# HCPL-3120_Gate_Driver_Circuit.net
KiCad netlist of a schematic drawn in Altium Designer
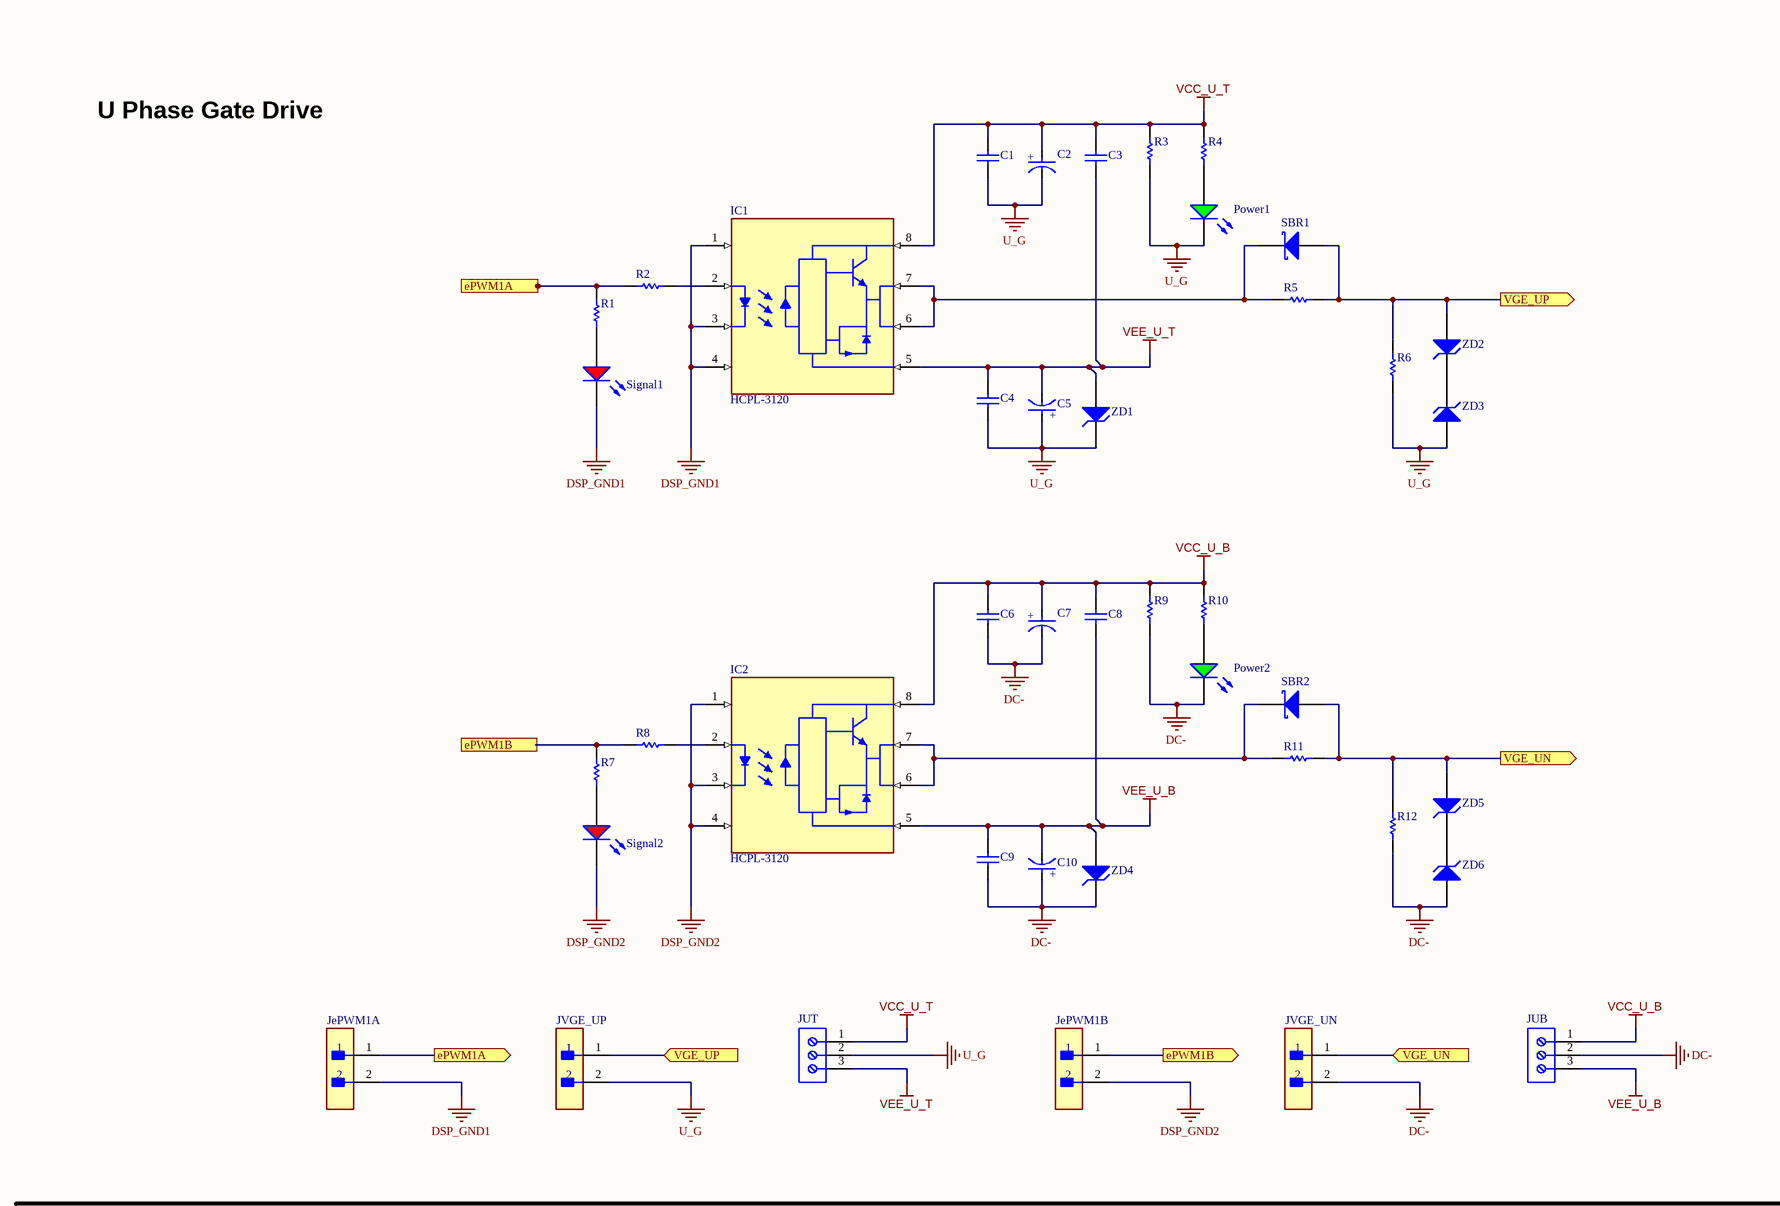
[diagram p0: HCPL-3120 Gate Driver Circuit.SchDoc, left]

(export (version "E")
  (design (tool "Eeschema 10.0.6"))
  (components
    (comp (ref "C1")
      (value "GRM188R71H104KA93D")
      (footprint "CAPC1608X90X35ML10T15")
      (description "Chip Capacitor, 0.1 uF, +/- 10%, 50 V, -55 to 125 degC, 0603 (1608 Metric), RoHS, Tape and Reel")
      (fields (field (name "TOLERANCE") "10%") (field (name "VOLTAGE") "50V"))
      (libsource (lib "Altium Content Vault") (part "CAP-NP-2"))
    )
    (comp (ref "C2")
      (value "EEUTA1H101")
      (footprint "FP-RAD-TH-D_10_0_5-L_12_5-MFG")
      (description "Aluminum Electrolytic Capacitors (Radial Lead Type) AEC-Q200 Qualified 100uF ±20% 50V")
      (fields (field (name "TOLERANCE") "20%"))
      (libsource (lib "Altium Content Vault") (part "203bc49f2ac43e59fd269a8c329ed05"))
    )
    (comp (ref "C3")
      (value "GRM188R71H104KA93D")
      (footprint "CAPC1608X90X35ML10T15")
      (description "Chip Capacitor, 0.1 uF, +/- 10%, 50 V, -55 to 125 degC, 0603 (1608 Metric), RoHS, Tape and Reel")
      (fields (field (name "TOLERANCE") "10%") (field (name "VOLTAGE") "50V"))
      (libsource (lib "Altium Content Vault") (part "CAP-NP-2"))
    )
    (comp (ref "C4")
      (value "GRM188R71H104KA93D")
      (footprint "CAPC1608X90X35ML10T15")
      (description "Chip Capacitor, 0.1 uF, +/- 10%, 50 V, -55 to 125 degC, 0603 (1608 Metric), RoHS, Tape and Reel")
      (fields (field (name "TOLERANCE") "10%") (field (name "VOLTAGE") "50V"))
      (libsource (lib "Altium Content Vault") (part "CAP-NP-2"))
    )
    (comp (ref "C5")
      (value "EEUTA1H101")
      (footprint "FP-RAD-TH-D_10_0_5-L_12_5-MFG")
      (description "Aluminum Electrolytic Capacitors (Radial Lead Type) AEC-Q200 Qualified 100uF ±20% 50V")
      (fields (field (name "TOLERANCE") "20%"))
      (libsource (lib "Altium Content Vault") (part "203bc49f2ac43e59fd269a8c329ed05"))
    )
    (comp (ref "C6")
      (value "GRM188R71H104KA93D")
      (footprint "CAPC1608X90X35ML10T15")
      (description "Chip Capacitor, 0.1 uF, +/- 10%, 50 V, -55 to 125 degC, 0603 (1608 Metric), RoHS, Tape and Reel")
      (fields (field (name "TOLERANCE") "10%") (field (name "VOLTAGE") "50V"))
      (libsource (lib "Altium Content Vault") (part "CAP-NP-2"))
    )
    (comp (ref "C7")
      (value "EEUTA1H101")
      (footprint "FP-RAD-TH-D_10_0_5-L_12_5-MFG")
      (description "Aluminum Electrolytic Capacitors (Radial Lead Type) AEC-Q200 Qualified 100uF ±20% 50V")
      (fields (field (name "TOLERANCE") "20%"))
      (libsource (lib "Altium Content Vault") (part "203bc49f2ac43e59fd269a8c329ed05"))
    )
    (comp (ref "C8")
      (value "GRM188R71H104KA93D")
      (footprint "CAPC1608X90X35ML10T15")
      (description "Chip Capacitor, 0.1 uF, +/- 10%, 50 V, -55 to 125 degC, 0603 (1608 Metric), RoHS, Tape and Reel")
      (fields (field (name "TOLERANCE") "10%") (field (name "VOLTAGE") "50V"))
      (libsource (lib "Altium Content Vault") (part "CAP-NP-2"))
    )
    (comp (ref "C9")
      (value "GRM188R71H104KA93D")
      (footprint "CAPC1608X90X35ML10T15")
      (description "Chip Capacitor, 0.1 uF, +/- 10%, 50 V, -55 to 125 degC, 0603 (1608 Metric), RoHS, Tape and Reel")
      (fields (field (name "TOLERANCE") "10%") (field (name "VOLTAGE") "50V"))
      (libsource (lib "Altium Content Vault") (part "CAP-NP-2"))
    )
    (comp (ref "C10")
      (value "EEUTA1H101")
      (footprint "FP-RAD-TH-D_10_0_5-L_12_5-MFG")
      (description "Aluminum Electrolytic Capacitors (Radial Lead Type) AEC-Q200 Qualified 100uF ±20% 50V")
      (fields (field (name "TOLERANCE") "20%"))
      (libsource (lib "Altium Content Vault") (part "203bc49f2ac43e59fd269a8c329ed05"))
    )
    (comp (ref "IC1")
      (value "HCPL-3120")
      (footprint "FP-DIP-8-MFG")
      (description "Optocoupler Drive Push-Pull 1-CH 30V 1500V 8-Pin PDIP Tube")
      (libsource (lib "HCPL_3210") (part "HCPL-3120"))
    )
    (comp (ref "IC2")
      (value "HCPL-3120")
      (footprint "FP-DIP-8-MFG")
      (description "Optocoupler Drive Push-Pull 1-CH 30V 1500V 8-Pin PDIP Tube")
      (libsource (lib "HCPL_3210") (part "HCPL-3120"))
    )
    (comp (ref "JePWM1A")
      (value "TSW-102-07-L-S")
      (footprint "FP-TSW-102-07-L-S-MFG")
      (description "CONN HEADER VERT 2POS 2.54MM")
      (libsource (lib "Altium Content Vault") (part "3bc925449376181038e59eaffc5286c"))
    )
    (comp (ref "JePWM1B")
      (value "TSW-102-07-L-S")
      (footprint "FP-TSW-102-07-L-S-MFG")
      (description "CONN HEADER VERT 2POS 2.54MM")
      (libsource (lib "Altium Content Vault") (part "3bc925449376181038e59eaffc5286c"))
    )
    (comp (ref "JUB")
      (value "691214110003")
      (footprint "691214110003")
      (fields (field (name "VOLTAGE") "300V"))
      (libsource (lib "Altium Content Vault") (part "TBL - 1R - 03P - Screw"))
    )
    (comp (ref "JUT")
      (value "691214110003")
      (footprint "691214110003")
      (fields (field (name "VOLTAGE") "300V"))
      (libsource (lib "Altium Content Vault") (part "TBL - 1R - 03P - Screw"))
    )
    (comp (ref "JVGE_UN")
      (value "TSW-102-07-L-S")
      (footprint "FP-TSW-102-07-L-S-MFG")
      (description "CONN HEADER VERT 2POS 2.54MM")
      (libsource (lib "Altium Content Vault") (part "3bc925449376181038e59eaffc5286c"))
    )
    (comp (ref "JVGE_UP")
      (value "TSW-102-07-L-S")
      (footprint "FP-TSW-102-07-L-S-MFG")
      (description "CONN HEADER VERT 2POS 2.54MM")
      (libsource (lib "Altium Content Vault") (part "3bc925449376181038e59eaffc5286c"))
    )
    (comp (ref "Power1")
      (value "151031VS04000")
      (footprint "WL-TMRC_D3.95H5.3")
      (description "Led, Green, T-1 (3Mm), 570 Nm, 2.1 V, 30 Ma, 120 Mcd")
      (libsource (lib "Altium Content Vault") (part "LED_Green_1A-2K"))
    )
    (comp (ref "Power2")
      (value "151031VS04000")
      (footprint "WL-TMRC_D3.95H5.3")
      (description "Led, Green, T-1 (3Mm), 570 Nm, 2.1 V, 30 Ma, 120 Mcd")
      (libsource (lib "Altium Content Vault") (part "LED_Green_1A-2K"))
    )
    (comp (ref "R1")
      (value "ERJ-8ENF1001V")
      (footprint "RESC3216X70X50LL05T20")
      (description "Res Thick Film 1206 1K Ohm 1% 0.25W(1/4W) ±100ppm/C Pad SMD Automotive T/R")
      (fields (field (name "MANUFACTURER") "Panasonic"))
      (libsource (lib "Altium Content Vault") (part "RES"))
    )
    (comp (ref "R2")
      (value "ERJ8ENF3300V")
      (footprint "RESC3216X70X50LL05T20")
      (description "Res Thick Film 1206 330 Ohm 1% 0.25W ±100ppm/°C Molded SMD Punched Carrier T/R")
      (fields (field (name "MANUFACTURER") "Panasonic"))
      (libsource (lib "Altium Content Vault") (part "RES"))
    )
    (comp (ref "R3")
      (value "ERJ-8ENF1001V")
      (footprint "RESC3216X70X50LL05T20")
      (description "Res Thick Film 1206 1K Ohm 1% 0.25W(1/4W) ±100ppm/C Pad SMD Automotive T/R")
      (fields (field (name "MANUFACTURER") "Panasonic"))
      (libsource (lib "Altium Content Vault") (part "RES"))
    )
    (comp (ref "R4")
      (value "ERJ-8ENF1001V")
      (footprint "RESC3216X70X50LL05T20")
      (description "Res Thick Film 1206 1K Ohm 1% 0.25W(1/4W) ±100ppm/C Pad SMD Automotive T/R")
      (fields (field (name "MANUFACTURER") "Panasonic"))
      (libsource (lib "Altium Content Vault") (part "RES"))
    )
    (comp (ref "R5")
      (value "ERJ-8ENF30R0V")
      (footprint "RESC3216X70X50NL05T20")
      (description "Res Thick Film 1206 30 Ohm 1% 0.25W ±100ppm/°C Molded SMD Punched Carrier T/R")
      (fields (field (name "MANUFACTURER") "Panasonic"))
      (libsource (lib "Altium Content Vault") (part "RES"))
    )
    (comp (ref "R6")
      (value "ERJ-8ENF1002V")
      (footprint "RESC3216X70X50LL05T20")
      (description "Res Thick Film 1206 10K Ohm 1% 0.25W(1/4W) ±100ppm/C Pad SMD Automotive T/R")
      (fields (field (name "MANUFACTURER") "Panasonic"))
      (libsource (lib "Altium Content Vault") (part "RES"))
    )
    (comp (ref "R7")
      (value "ERJ-8ENF1001V")
      (footprint "RESC3216X70X50LL05T20")
      (description "Res Thick Film 1206 1K Ohm 1% 0.25W(1/4W) ±100ppm/C Pad SMD Automotive T/R")
      (fields (field (name "MANUFACTURER") "Panasonic"))
      (libsource (lib "Altium Content Vault") (part "RES"))
    )
    (comp (ref "R8")
      (value "ERJ8ENF3300V")
      (footprint "RESC3216X70X50LL05T20")
      (description "Res Thick Film 1206 330 Ohm 1% 0.25W ±100ppm/°C Molded SMD Punched Carrier T/R")
      (fields (field (name "MANUFACTURER") "Panasonic"))
      (libsource (lib "Altium Content Vault") (part "RES"))
    )
    (comp (ref "R9")
      (value "ERJ-8ENF1001V")
      (footprint "RESC3216X70X50LL05T20")
      (description "Res Thick Film 1206 1K Ohm 1% 0.25W(1/4W) ±100ppm/C Pad SMD Automotive T/R")
      (fields (field (name "MANUFACTURER") "Panasonic"))
      (libsource (lib "Altium Content Vault") (part "RES"))
    )
    (comp (ref "R10")
      (value "ERJ-8ENF1001V")
      (footprint "RESC3216X70X50LL05T20")
      (description "Res Thick Film 1206 1K Ohm 1% 0.25W(1/4W) ±100ppm/C Pad SMD Automotive T/R")
      (fields (field (name "MANUFACTURER") "Panasonic"))
      (libsource (lib "Altium Content Vault") (part "RES"))
    )
    (comp (ref "R11")
      (value "ERJ-8ENF30R0V")
      (footprint "RESC3216X70X50NL05T20")
      (description "Res Thick Film 1206 30 Ohm 1% 0.25W ±100ppm/°C Molded SMD Punched Carrier T/R")
      (fields (field (name "MANUFACTURER") "Panasonic"))
      (libsource (lib "Altium Content Vault") (part "RES"))
    )
    (comp (ref "R12")
      (value "ERJ-8ENF1002V")
      (footprint "RESC3216X70X50LL05T20")
      (description "Res Thick Film 1206 10K Ohm 1% 0.25W(1/4W) ±100ppm/C Pad SMD Automotive T/R")
      (fields (field (name "MANUFACTURER") "Panasonic"))
      (libsource (lib "Altium Content Vault") (part "RES"))
    )
    (comp (ref "SBR1")
      (value "DFLS130L-7")
      (footprint "DIOD-POWERDI123-2_A_V")
      (description "Schottky Barrier Rectifier, 30 V, 1 A, -40 to 125 degC, 2-Pin SMD, RoHS, Tape and Reel")
      (fields (field (name "MANUFACTURER") "Diodes Inc"))
      (libsource (lib "Altium Content Vault") (part "DSKY-AK-2"))
    )
    (comp (ref "SBR2")
      (value "DFLS130L-7")
      (footprint "DIOD-POWERDI123-2_A_V")
      (description "Schottky Barrier Rectifier, 30 V, 1 A, -40 to 125 degC, 2-Pin SMD, RoHS, Tape and Reel")
      (fields (field (name "MANUFACTURER") "Diodes Inc"))
      (libsource (lib "Altium Content Vault") (part "DSKY-AK-2"))
    )
    (comp (ref "Signal1")
      (value "151031SS04000")
      (footprint "WL-TMRC_D3.95H5.3")
      (description "Led, Red, T-1 (3Mm), 635 Nm, 2 V, 30 Ma, 160 Mcd")
      (libsource (lib "Altium Content Vault") (part "LED_Red_1A-2K"))
    )
    (comp (ref "Signal2")
      (value "151031SS04000")
      (footprint "WL-TMRC_D3.95H5.3")
      (description "Led, Red, T-1 (3Mm), 635 Nm, 2 V, 30 Ma, 160 Mcd")
      (libsource (lib "Altium Content Vault") (part "LED_Red_1A-2K"))
    )
    (comp (ref "ZD1")
      (value "MMSZ4688T1G")
      (footprint "ONSC-SOD-123-2-425-04_V")
      (description "Zener Voltage Regulator, 500 mW, 2-Pin SOD-123, Pb-Free, Tape and Reel")
      (fields (field (name "MANUFACTURER") "On Semiconductor"))
      (libsource (lib "Altium Content Vault") (part "ONSC-K1A2-2"))
    )
    (comp (ref "ZD2")
      (value "SZMMSZ4702T1G")
      (footprint "ONSC-SOD-123-2-425-04_V")
      (description "Zener Voltage Regulator, 500 mW, 2-Pin SOD-123, Pb-Free, Tape and Reel")
      (fields (field (name "MANUFACTURER") "On Semiconductor"))
      (libsource (lib "Altium Content Vault") (part "ONSC-K1A2-2"))
    )
    (comp (ref "ZD3")
      (value "SZMMSZ4702T1G")
      (footprint "ONSC-SOD-123-2-425-04_V")
      (description "Zener Voltage Regulator, 500 mW, 2-Pin SOD-123, Pb-Free, Tape and Reel")
      (fields (field (name "MANUFACTURER") "On Semiconductor"))
      (libsource (lib "Altium Content Vault") (part "ONSC-K1A2-2"))
    )
    (comp (ref "ZD4")
      (value "MMSZ4688T1G")
      (footprint "ONSC-SOD-123-2-425-04_V")
      (description "Zener Voltage Regulator, 500 mW, 2-Pin SOD-123, Pb-Free, Tape and Reel")
      (fields (field (name "MANUFACTURER") "On Semiconductor"))
      (libsource (lib "Altium Content Vault") (part "ONSC-K1A2-2"))
    )
    (comp (ref "ZD5")
      (value "SZMMSZ4702T1G")
      (footprint "ONSC-SOD-123-2-425-04_V")
      (description "Zener Voltage Regulator, 500 mW, 2-Pin SOD-123, Pb-Free, Tape and Reel")
      (fields (field (name "MANUFACTURER") "On Semiconductor"))
      (libsource (lib "Altium Content Vault") (part "ONSC-K1A2-2"))
    )
    (comp (ref "ZD6")
      (value "SZMMSZ4702T1G")
      (footprint "ONSC-SOD-123-2-425-04_V")
      (description "Zener Voltage Regulator, 500 mW, 2-Pin SOD-123, Pb-Free, Tape and Reel")
      (fields (field (name "MANUFACTURER") "On Semiconductor"))
      (libsource (lib "Altium Content Vault") (part "ONSC-K1A2-2"))
    )
  )
  (nets
    (net (code "1") (name "/VGE_UN") (class "Default")
      (node (ref "JVGE_UN") (pin "1") (pinfunction "1_1") (pintype "passive"))
      (node (ref "R11") (pin "2") (pinfunction "2_2") (pintype "passive"))
      (node (ref "R12") (pin "1") (pinfunction "1_1") (pintype "passive"))
      (node (ref "SBR2") (pin "1") (pinfunction "A_1") (pintype "passive"))
      (node (ref "ZD5") (pin "2") (pinfunction "A_2") (pintype "passive"))
    )
    (net (code "2") (name "/VGE_UP") (class "Default")
      (node (ref "JVGE_UP") (pin "1") (pinfunction "1_1") (pintype "passive"))
      (node (ref "R5") (pin "2") (pinfunction "2_2") (pintype "passive"))
      (node (ref "R6") (pin "1") (pinfunction "1_1") (pintype "passive"))
      (node (ref "SBR1") (pin "1") (pinfunction "A_1") (pintype "passive"))
      (node (ref "ZD2") (pin "2") (pinfunction "A_2") (pintype "passive"))
    )
    (net (code "3") (name "/ePWM1A") (class "Default")
      (node (ref "JePWM1A") (pin "1") (pinfunction "1_1") (pintype "passive"))
      (node (ref "R1") (pin "1") (pinfunction "1_1") (pintype "passive"))
      (node (ref "R2") (pin "1") (pinfunction "1_1") (pintype "passive"))
    )
    (net (code "4") (name "/ePWM1B") (class "Default")
      (node (ref "JePWM1B") (pin "1") (pinfunction "1_1") (pintype "passive"))
      (node (ref "R7") (pin "1") (pinfunction "1_1") (pintype "passive"))
      (node (ref "R8") (pin "1") (pinfunction "1_1") (pintype "passive"))
    )
    (net (code "5") (name "DC-") (class "Default")
      (node (ref "C10") (pin "2") (pinfunction "A_2") (pintype "passive"))
      (node (ref "C6") (pin "2") (pinfunction "2_2") (pintype "passive"))
      (node (ref "C7") (pin "1") (pinfunction "C_1") (pintype "passive"))
      (node (ref "C9") (pin "2") (pinfunction "2_2") (pintype "passive"))
      (node (ref "JUB") (pin "2") (pinfunction "2_2") (pintype "passive"))
      (node (ref "JVGE_UN") (pin "2") (pinfunction "2_2") (pintype "passive"))
      (node (ref "Power2") (pin "2") (pinfunction "K_2") (pintype "passive"))
      (node (ref "R12") (pin "2") (pinfunction "2_2") (pintype "passive"))
      (node (ref "R9") (pin "2") (pinfunction "2_2") (pintype "passive"))
      (node (ref "ZD4") (pin "1") (pinfunction "K_1") (pintype "passive"))
      (node (ref "ZD6") (pin "2") (pinfunction "A_2") (pintype "passive"))
    )
    (net (code "6") (name "DSP_GND1") (class "Default")
      (node (ref "IC1") (pin "1") (pinfunction "N/C_1") (pintype "input"))
      (node (ref "IC1") (pin "3") (pinfunction "CATHODE_3") (pintype "input"))
      (node (ref "IC1") (pin "4") (pinfunction "N/C_4") (pintype "input"))
      (node (ref "JePWM1A") (pin "2") (pinfunction "2_2") (pintype "passive"))
      (node (ref "Signal1") (pin "2") (pinfunction "K_2") (pintype "passive"))
    )
    (net (code "7") (name "DSP_GND2") (class "Default")
      (node (ref "IC2") (pin "1") (pinfunction "N/C_1") (pintype "input"))
      (node (ref "IC2") (pin "3") (pinfunction "CATHODE_3") (pintype "input"))
      (node (ref "IC2") (pin "4") (pinfunction "N/C_4") (pintype "input"))
      (node (ref "JePWM1B") (pin "2") (pinfunction "2_2") (pintype "passive"))
      (node (ref "Signal2") (pin "2") (pinfunction "K_2") (pintype "passive"))
    )
    (net (code "8") (name "Net-(IC1-ANODE)") (class "Default")
      (node (ref "IC1") (pin "2") (pinfunction "ANODE_2") (pintype "input"))
      (node (ref "R2") (pin "2") (pinfunction "2_2") (pintype "passive"))
    )
    (net (code "9") (name "Net-(IC2-ANODE)") (class "Default")
      (node (ref "IC2") (pin "2") (pinfunction "ANODE_2") (pintype "input"))
      (node (ref "R8") (pin "2") (pinfunction "2_2") (pintype "passive"))
    )
    (net (code "10") (name "Net-(Power1-A)") (class "Default")
      (node (ref "Power1") (pin "1") (pinfunction "A_1") (pintype "passive"))
      (node (ref "R4") (pin "2") (pinfunction "2_2") (pintype "passive"))
    )
    (net (code "11") (name "Net-(Power2-A)") (class "Default")
      (node (ref "Power2") (pin "1") (pinfunction "A_1") (pintype "passive"))
      (node (ref "R10") (pin "2") (pinfunction "2_2") (pintype "passive"))
    )
    (net (code "12") (name "Net-(SBR1-K)") (class "Default")
      (node (ref "IC1") (pin "6") (pinfunction "VO_6") (pintype "input"))
      (node (ref "IC1") (pin "7") (pinfunction "VO_7") (pintype "input"))
      (node (ref "R5") (pin "1") (pinfunction "1_1") (pintype "passive"))
      (node (ref "SBR1") (pin "2") (pinfunction "K_2") (pintype "passive"))
    )
    (net (code "13") (name "Net-(SBR2-K)") (class "Default")
      (node (ref "IC2") (pin "6") (pinfunction "VO_6") (pintype "input"))
      (node (ref "IC2") (pin "7") (pinfunction "VO_7") (pintype "input"))
      (node (ref "R11") (pin "1") (pinfunction "1_1") (pintype "passive"))
      (node (ref "SBR2") (pin "2") (pinfunction "K_2") (pintype "passive"))
    )
    (net (code "14") (name "Net-(Signal1-A)") (class "Default")
      (node (ref "R1") (pin "2") (pinfunction "2_2") (pintype "passive"))
      (node (ref "Signal1") (pin "1") (pinfunction "A_1") (pintype "passive"))
    )
    (net (code "15") (name "Net-(Signal2-A)") (class "Default")
      (node (ref "R7") (pin "2") (pinfunction "2_2") (pintype "passive"))
      (node (ref "Signal2") (pin "1") (pinfunction "A_1") (pintype "passive"))
    )
    (net (code "16") (name "Net-(ZD2-K)") (class "Default")
      (node (ref "ZD2") (pin "1") (pinfunction "K_1") (pintype "passive"))
      (node (ref "ZD3") (pin "1") (pinfunction "K_1") (pintype "passive"))
    )
    (net (code "17") (name "Net-(ZD5-K)") (class "Default")
      (node (ref "ZD5") (pin "1") (pinfunction "K_1") (pintype "passive"))
      (node (ref "ZD6") (pin "1") (pinfunction "K_1") (pintype "passive"))
    )
    (net (code "18") (name "U_G") (class "Default")
      (node (ref "C1") (pin "2") (pinfunction "2_2") (pintype "passive"))
      (node (ref "C2") (pin "1") (pinfunction "C_1") (pintype "passive"))
      (node (ref "C4") (pin "2") (pinfunction "2_2") (pintype "passive"))
      (node (ref "C5") (pin "2") (pinfunction "A_2") (pintype "passive"))
      (node (ref "JUT") (pin "2") (pinfunction "2_2") (pintype "passive"))
      (node (ref "JVGE_UP") (pin "2") (pinfunction "2_2") (pintype "passive"))
      (node (ref "Power1") (pin "2") (pinfunction "K_2") (pintype "passive"))
      (node (ref "R3") (pin "2") (pinfunction "2_2") (pintype "passive"))
      (node (ref "R6") (pin "2") (pinfunction "2_2") (pintype "passive"))
      (node (ref "ZD1") (pin "1") (pinfunction "K_1") (pintype "passive"))
      (node (ref "ZD3") (pin "2") (pinfunction "A_2") (pintype "passive"))
    )
    (net (code "19") (name "VCC_U_B") (class "Default")
      (node (ref "C6") (pin "1") (pinfunction "1_1") (pintype "passive"))
      (node (ref "C7") (pin "2") (pinfunction "A_2") (pintype "passive"))
      (node (ref "C8") (pin "1") (pinfunction "1_1") (pintype "passive"))
      (node (ref "IC2") (pin "8") (pinfunction "VCC_8") (pintype "input"))
      (node (ref "JUB") (pin "1") (pinfunction "1_1") (pintype "passive"))
      (node (ref "R10") (pin "1") (pinfunction "1_1") (pintype "passive"))
      (node (ref "R9") (pin "1") (pinfunction "1_1") (pintype "passive"))
    )
    (net (code "20") (name "VCC_U_T") (class "Default")
      (node (ref "C1") (pin "1") (pinfunction "1_1") (pintype "passive"))
      (node (ref "C2") (pin "2") (pinfunction "A_2") (pintype "passive"))
      (node (ref "C3") (pin "1") (pinfunction "1_1") (pintype "passive"))
      (node (ref "IC1") (pin "8") (pinfunction "VCC_8") (pintype "input"))
      (node (ref "JUT") (pin "1") (pinfunction "1_1") (pintype "passive"))
      (node (ref "R3") (pin "1") (pinfunction "1_1") (pintype "passive"))
      (node (ref "R4") (pin "1") (pinfunction "1_1") (pintype "passive"))
    )
    (net (code "21") (name "VEE_U_B") (class "Default")
      (node (ref "C10") (pin "1") (pinfunction "C_1") (pintype "passive"))
      (node (ref "C8") (pin "2") (pinfunction "2_2") (pintype "passive"))
      (node (ref "C9") (pin "1") (pinfunction "1_1") (pintype "passive"))
      (node (ref "IC2") (pin "5") (pinfunction "VEE_5") (pintype "input"))
      (node (ref "JUB") (pin "3") (pinfunction "3_3") (pintype "passive"))
      (node (ref "ZD4") (pin "2") (pinfunction "A_2") (pintype "passive"))
    )
    (net (code "22") (name "VEE_U_T") (class "Default")
      (node (ref "C3") (pin "2") (pinfunction "2_2") (pintype "passive"))
      (node (ref "C4") (pin "1") (pinfunction "1_1") (pintype "passive"))
      (node (ref "C5") (pin "1") (pinfunction "C_1") (pintype "passive"))
      (node (ref "IC1") (pin "5") (pinfunction "VEE_5") (pintype "input"))
      (node (ref "JUT") (pin "3") (pinfunction "3_3") (pintype "passive"))
      (node (ref "ZD1") (pin "2") (pinfunction "A_2") (pintype "passive"))
    )
  )
)
